# FMC.net
KiCad netlist of a schematic drawn in Altium Designer
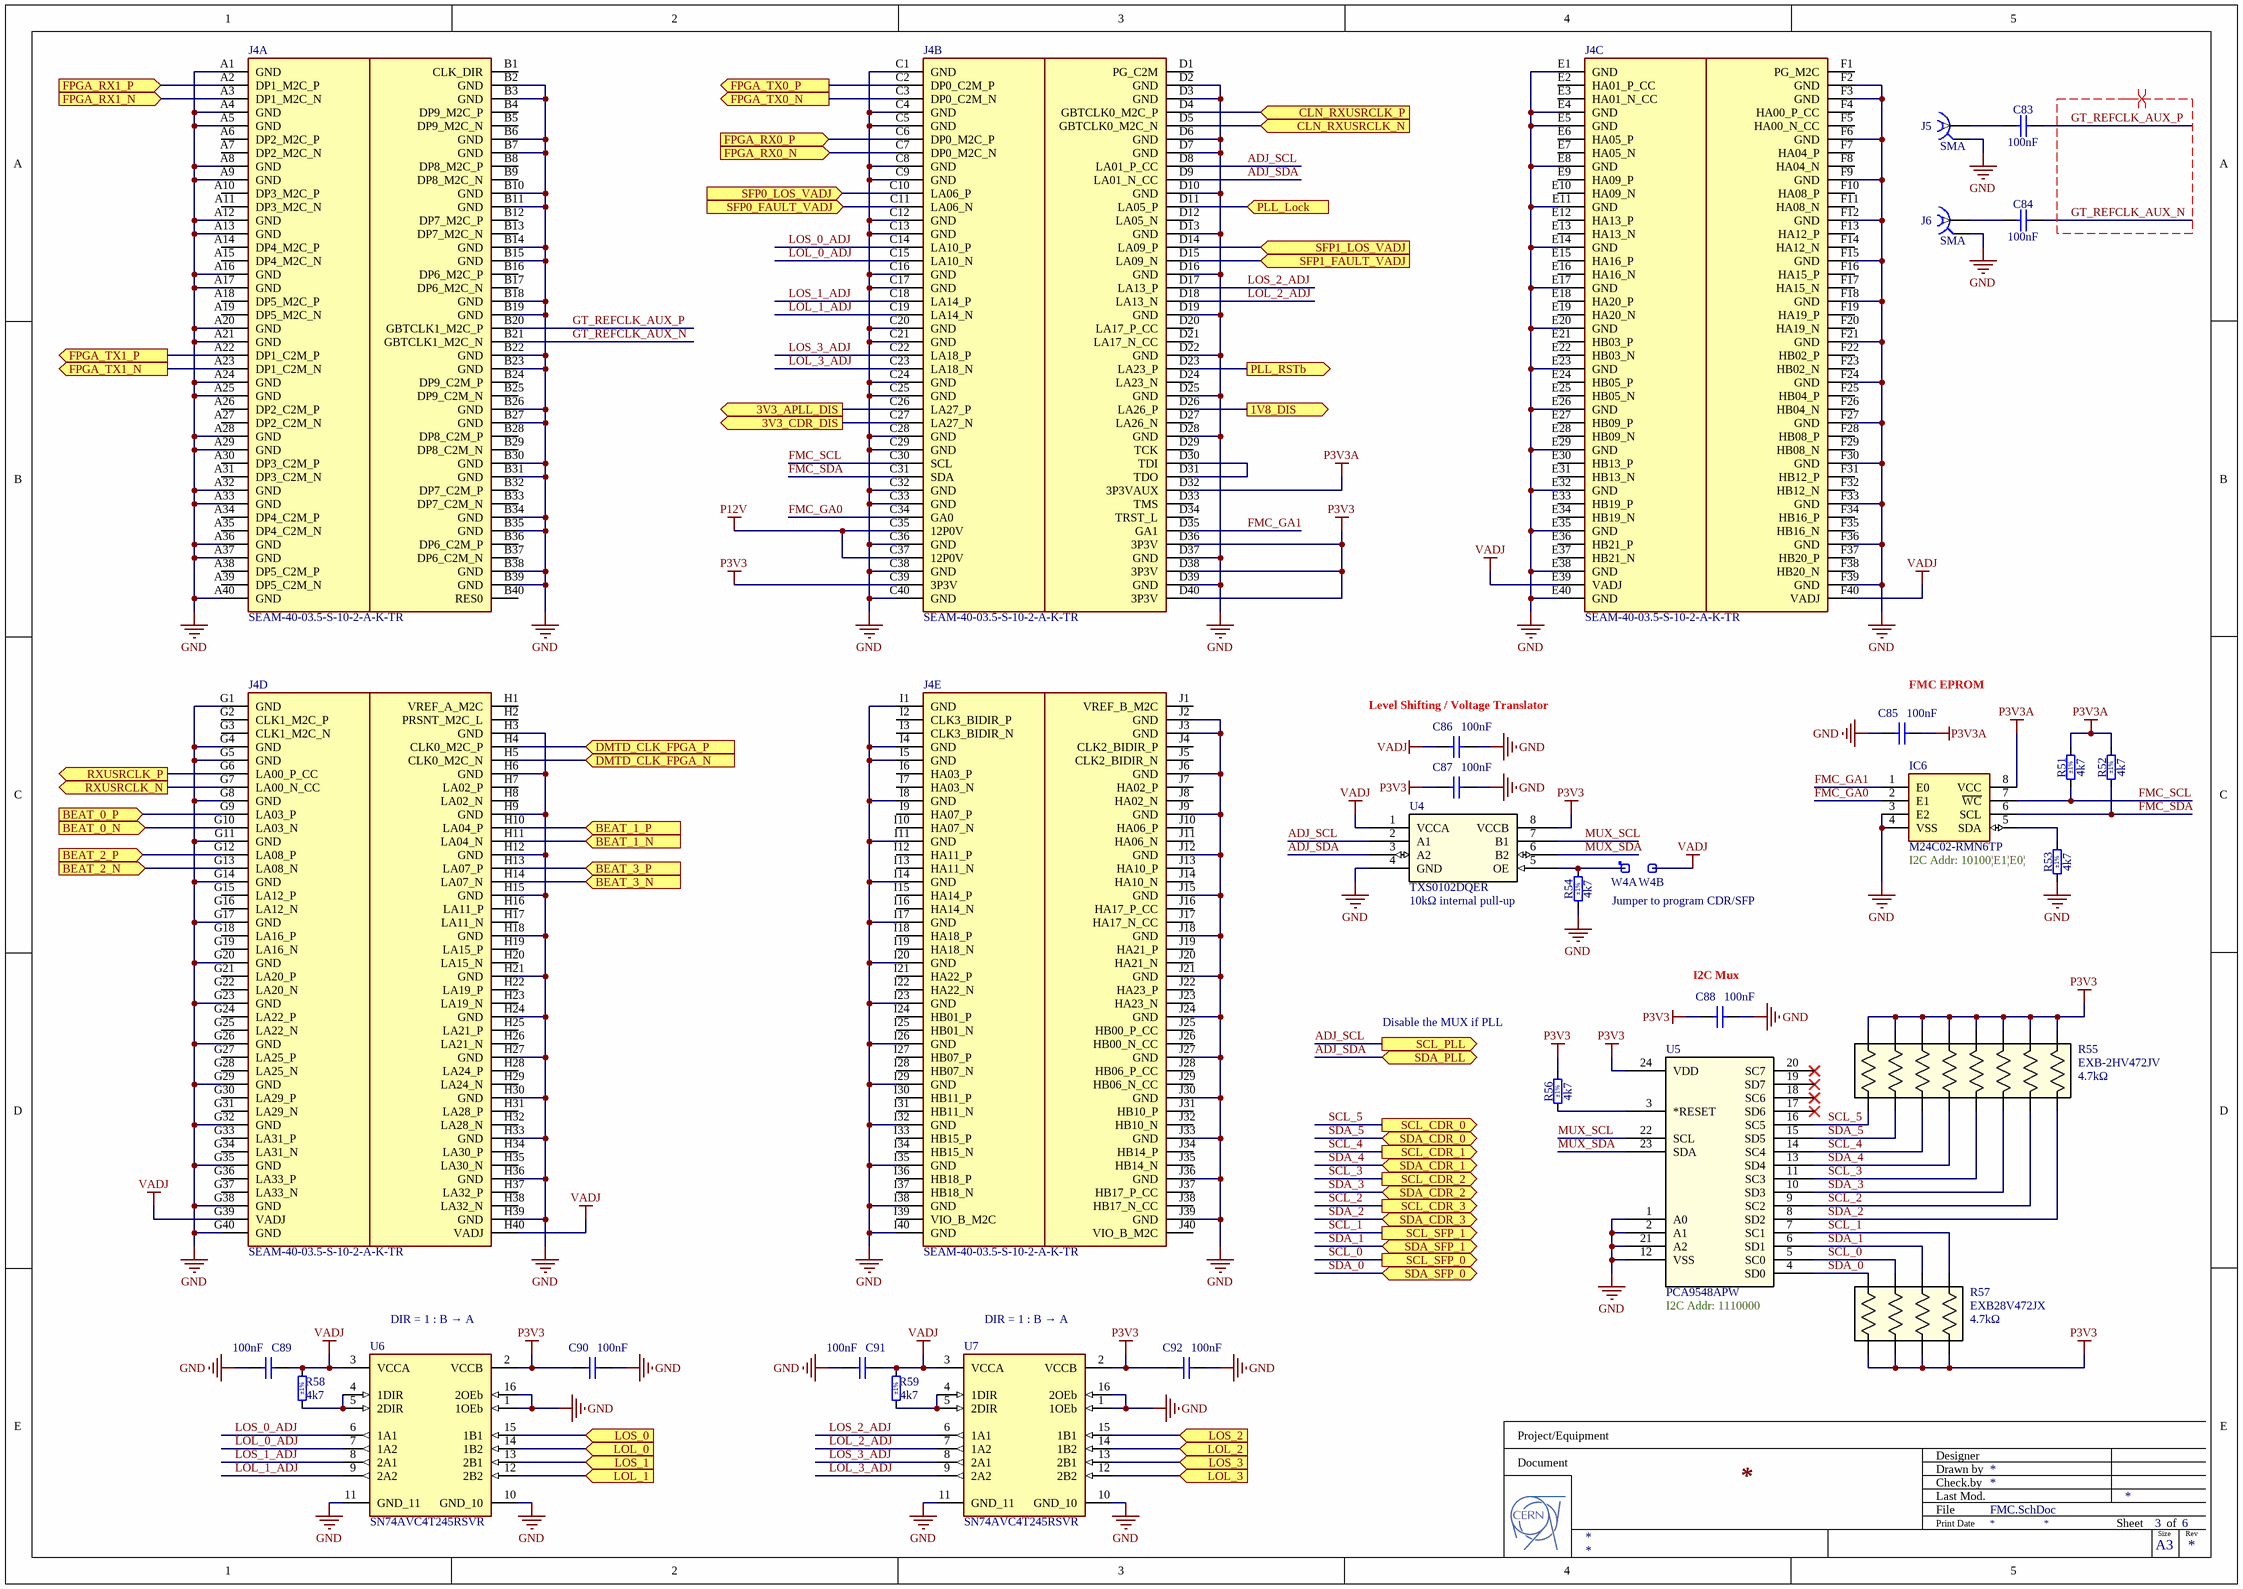
[diagram p0: FMC.SchDoc]

(export (version "E")
  (design (tool "Eeschema 10.0.6"))
  (components
    (comp (ref "C83")
      (value "100nF")
      (footprint "CAPC0603X33N")
      (description "Non-polarised capacitor")
      (fields
        (field (name "PART NUMBER") "CC0201_100NF_6.3V_10%_X7R")
        (field (name "VOLTAGE") "6.3V")
        (field (name "AUTHOR") "CERN DEM BC")
      )
      (libsource (lib "Capacitors") (part "Capacitor - non polarized"))
    )
    (comp (ref "C84")
      (value "100nF")
      (footprint "CAPC0603X33N")
      (description "Non-polarised capacitor")
      (fields
        (field (name "PART NUMBER") "CC0201_100NF_6.3V_10%_X7R")
        (field (name "VOLTAGE") "6.3V")
        (field (name "AUTHOR") "CERN DEM BC")
      )
      (libsource (lib "Capacitors") (part "Capacitor - non polarized"))
    )
    (comp (ref "C85")
      (value "100nF")
      (footprint "CAPC0603X33N")
      (description "GRM033R61C104KE14")
      (fields
        (field (name "PART NUMBER") "CC0201_100NF_6.3V_10%_X5R")
        (field (name "VOLTAGE") "6.3V")
        (field (name "AUTHOR") "CERN DEM JLC")
      )
      (libsource (lib "Capacitors") (part "Capacitor - non polarized"))
    )
    (comp (ref "C86")
      (value "100nF")
      (footprint "CAPC0603X33N")
      (description "GRM033R61C104KE14")
      (fields
        (field (name "PART NUMBER") "CC0201_100NF_6.3V_10%_X5R")
        (field (name "VOLTAGE") "6.3V")
        (field (name "AUTHOR") "CERN DEM JLC")
      )
      (libsource (lib "Capacitors") (part "Capacitor - non polarized"))
    )
    (comp (ref "C87")
      (value "100nF")
      (footprint "CAPC0603X33N")
      (description "GRM033R61C104KE14")
      (fields
        (field (name "PART NUMBER") "CC0201_100NF_6.3V_10%_X5R")
        (field (name "VOLTAGE") "6.3V")
        (field (name "AUTHOR") "CERN DEM JLC")
      )
      (libsource (lib "Capacitors") (part "Capacitor - non polarized"))
    )
    (comp (ref "C88")
      (value "100nF")
      (footprint "CAPC0603X33N")
      (description "GRM033R61C104KE14")
      (fields
        (field (name "PART NUMBER") "CC0201_100NF_6.3V_10%_X5R")
        (field (name "VOLTAGE") "6.3V")
        (field (name "AUTHOR") "CERN DEM JLC")
      )
      (libsource (lib "Capacitors") (part "Capacitor - non polarized"))
    )
    (comp (ref "C89")
      (value "100nF")
      (footprint "CAPC0603X33N")
      (description "GRM033R61C104KE14")
      (fields
        (field (name "PART NUMBER") "CC0201_100NF_6.3V_10%_X5R")
        (field (name "VOLTAGE") "6.3V")
        (field (name "AUTHOR") "CERN DEM JLC")
      )
      (libsource (lib "Capacitors") (part "Capacitor - non polarized"))
    )
    (comp (ref "C90")
      (value "100nF")
      (footprint "CAPC0603X33N")
      (description "GRM033R61C104KE14")
      (fields
        (field (name "PART NUMBER") "CC0201_100NF_6.3V_10%_X5R")
        (field (name "VOLTAGE") "6.3V")
        (field (name "AUTHOR") "CERN DEM JLC")
      )
      (libsource (lib "Capacitors") (part "Capacitor - non polarized"))
    )
    (comp (ref "C91")
      (value "100nF")
      (footprint "CAPC0603X33N")
      (description "GRM033R61C104KE14")
      (fields
        (field (name "PART NUMBER") "CC0201_100NF_6.3V_10%_X5R")
        (field (name "VOLTAGE") "6.3V")
        (field (name "AUTHOR") "CERN DEM JLC")
      )
      (libsource (lib "Capacitors") (part "Capacitor - non polarized"))
    )
    (comp (ref "C92")
      (value "100nF")
      (footprint "CAPC0603X33N")
      (description "GRM033R61C104KE14")
      (fields
        (field (name "PART NUMBER") "CC0201_100NF_6.3V_10%_X5R")
        (field (name "VOLTAGE") "6.3V")
        (field (name "AUTHOR") "CERN DEM JLC")
      )
      (libsource (lib "Capacitors") (part "Capacitor - non polarized"))
    )
    (comp (ref "IC6")
      (value "M24C02-RMN6TP")
      (footprint "SamacSys:SOIC127P600X175-8N")
      (description "Integrated Circuit")
      (fields (field (name "MOUSER PART NUMBER") "511-M24C02-RMN6TP"))
      (libsource (lib "SamacSys") (part "M24C02-RMN6TP"))
    )
    (comp (ref "J4")
      (value "SEAM-40-03.5-S-10-2-A-K-TR")
      (footprint "SAMTEC_SEAM-40-03.5-S-10-2-A-K-TR")
      (fields (field (name "MF") "Samtec"))
      (libsource (lib "SEAM-40-03.5-S-10-2-A-K-TR") (part "SEAM-40-03.5-S-10-2-A-K-TR"))
    )
    (comp (ref "J5")
      (value "SMA")
      (footprint "SAMTEC_SMA-J-P-H-ST-MT1")
      (fields
        (field (name "PART NUMBER") "SAMTEC_SMA-J-P-H-ST-MT1")
        (field (name "MANUFACTURER") "SAMTEC")
        (field (name "MANUFACTURER PART NUMBER") "SMA-J-P-H-ST-MT1")
        (field (name "AUTHOR") "CERN DEM HF")
      )
      (libsource (lib "Connectors") (part "Coax_1Female_1Shield"))
    )
    (comp (ref "J6")
      (value "SMA")
      (footprint "SAMTEC_SMA-J-P-H-ST-MT1")
      (fields
        (field (name "PART NUMBER") "SAMTEC_SMA-J-P-H-ST-MT1")
        (field (name "MANUFACTURER") "SAMTEC")
        (field (name "MANUFACTURER PART NUMBER") "SMA-J-P-H-ST-MT1")
        (field (name "AUTHOR") "CERN DEM HF")
      )
      (libsource (lib "Connectors") (part "Coax_1Female_1Shield"))
    )
    (comp (ref "R51")
      (value "4k7")
      (footprint "RESC1005X40N")
      (description "Resistor - 1%")
      (fields
        (field (name "TOLERANCE") "±1%")
        (field (name "PART NUMBER") "R0402_4K7_1%_0.0625W_100PPM")
        (field (name "POWER") "0.0625W")
        (field (name "AUTHOR") "CERN DEM JLC")
      )
      (libsource (lib "Resistors") (part "Resistor - 1%"))
    )
    (comp (ref "R52")
      (value "4k7")
      (footprint "RESC1005X40N")
      (description "Resistor - 1%")
      (fields
        (field (name "TOLERANCE") "±1%")
        (field (name "PART NUMBER") "R0402_4K7_1%_0.0625W_100PPM")
        (field (name "POWER") "0.0625W")
        (field (name "AUTHOR") "CERN DEM JLC")
      )
      (libsource (lib "Resistors") (part "Resistor - 1%"))
    )
    (comp (ref "R53")
      (value "4k7")
      (footprint "RESC1005X40N")
      (description "Resistor - 1%")
      (fields
        (field (name "TOLERANCE") "±1%")
        (field (name "PART NUMBER") "R0402_4K7_1%_0.0625W_100PPM")
        (field (name "POWER") "0.0625W")
        (field (name "AUTHOR") "CERN DEM JLC")
      )
      (libsource (lib "Resistors") (part "Resistor - 1%"))
    )
    (comp (ref "R54")
      (value "4k7")
      (footprint "RESC1005X40N")
      (description "Resistor - 1%")
      (fields
        (field (name "TOLERANCE") "±1%")
        (field (name "PART NUMBER") "R0402_4K7_1%_0.0625W_100PPM")
        (field (name "POWER") "0.0625W")
        (field (name "AUTHOR") "CERN DEM JLC")
      )
      (libsource (lib "Resistors") (part "Resistor - 1%"))
    )
    (comp (ref "R55")
      (value "EXB-2HV472JV")
      (footprint "RES_EXB2HV")
      (description "No Description Available")
      (libsource (lib "EXB-2HV472JV") (part "EXB-2HV472JV"))
    )
    (comp (ref "R56")
      (value "4k7")
      (footprint "RESC1005X40N")
      (description "Resistor - 1%")
      (fields
        (field (name "TOLERANCE") "±1%")
        (field (name "PART NUMBER") "R0402_4K7_1%_0.0625W_100PPM")
        (field (name "POWER") "0.0625W")
        (field (name "AUTHOR") "CERN DEM JLC")
      )
      (libsource (lib "Resistors") (part "Resistor - 1%"))
    )
    (comp (ref "R57")
      (value "EXB28V472JX")
      (footprint "C_ARRAY_EXB28V_PAN")
      (description "No Description Available")
      (libsource (lib "EXB28V472JX") (part "EXB28V472JX"))
    )
    (comp (ref "R58")
      (value "4k7")
      (footprint "RESC1005X40N")
      (description "Resistor - 1%")
      (fields
        (field (name "TOLERANCE") "±1%")
        (field (name "PART NUMBER") "R0402_4K7_1%_0.0625W_100PPM")
        (field (name "POWER") "0.0625W")
        (field (name "AUTHOR") "CERN DEM JLC")
      )
      (libsource (lib "Resistors") (part "Resistor - 1%"))
    )
    (comp (ref "R59")
      (value "4k7")
      (footprint "RESC1005X40N")
      (description "Resistor - 1%")
      (fields
        (field (name "TOLERANCE") "±1%")
        (field (name "PART NUMBER") "R0402_4K7_1%_0.0625W_100PPM")
        (field (name "POWER") "0.0625W")
        (field (name "AUTHOR") "CERN DEM JLC")
      )
      (libsource (lib "Resistors") (part "Resistor - 1%"))
    )
    (comp (ref "U4")
      (value "TXS0102DQER")
      (footprint "TXS0102DQER:DQE8_TEX")
      (description "No Description Available")
      (libsource (lib "TXS0102DQER") (part "TXS0102DQER"))
    )
    (comp (ref "U5")
      (value "PCA9548APW")
      (footprint "PCA9548APW:SOT355-1_NXP")
      (description "No Description Available")
      (libsource (lib "PCA9548APW") (part "PCA9548APW"))
    )
    (comp (ref "U6")
      (value "SN74AVC4T245RSVR")
      (footprint "QFN40P260X180X55-16N:QFN40P260X180X55-16N")
      (fields (field (name "MF") "Texas Instruments"))
      (libsource (lib "SN74AVC4T245RSVR") (part "SN74AVC4T245RSVR"))
    )
    (comp (ref "U7")
      (value "SN74AVC4T245RSVR")
      (footprint "QFN40P260X180X55-16N:QFN40P260X180X55-16N")
      (fields (field (name "MF") "Texas Instruments"))
      (libsource (lib "SN74AVC4T245RSVR") (part "SN74AVC4T245RSVR"))
    )
    (comp (ref "W4")
      (value "Header 2")
      (footprint "SAMTEC_HTSW-102-23-L-S")
      (description "2 Mini Wire-Wrap Contact Strip Header")
      (fields
        (field (name "PART NUMBER") "SAMTEC_HTSW-102-23-L-S")
        (field (name "MANUFACTURER") "SAMTEC")
        (field (name "AUTHOR") "CERN DEM JLC")
      )
      (libsource (lib "Connectors") (part "Wire-Wrap Contact x2"))
    )
  )
  (nets
    (net (code "1") (name "/1V8_DIS") (class "Default")
      (node (ref "J4") (pin "D26") (pinfunction "LA26_P_D26") (pintype "passive"))
    )
    (net (code "2") (name "/3V3_APLL_DIS") (class "Default")
      (node (ref "J4") (pin "C26") (pinfunction "LA27_P_C26") (pintype "passive"))
    )
    (net (code "3") (name "/3V3_CDR_DIS") (class "Default")
      (node (ref "J4") (pin "C27") (pinfunction "LA27_N_C27") (pintype "passive"))
    )
    (net (code "4") (name "/ADJ_SCL") (class "Default")
      (node (ref "J4") (pin "D8") (pinfunction "LA01_P_CC_D8") (pintype "passive"))
      (node (ref "U4") (pin "2") (pinfunction "A1_2") (pintype "passive"))
    )
    (net (code "5") (name "/ADJ_SDA") (class "Default")
      (node (ref "J4") (pin "D9") (pinfunction "LA01_N_CC_D9") (pintype "passive"))
      (node (ref "U4") (pin "3") (pinfunction "A2_3") (pintype "bidirectional"))
    )
    (net (code "6") (name "/BEAT_0_N") (class "Default")
      (node (ref "J4") (pin "G10") (pinfunction "LA03_N_G10") (pintype "passive"))
    )
    (net (code "7") (name "/BEAT_0_P") (class "Default")
      (node (ref "J4") (pin "G9") (pinfunction "LA03_P_G9") (pintype "passive"))
    )
    (net (code "8") (name "/BEAT_1_N") (class "Default")
      (node (ref "J4") (pin "H11") (pinfunction "LA04_N_H11") (pintype "passive"))
    )
    (net (code "9") (name "/BEAT_1_P") (class "Default")
      (node (ref "J4") (pin "H10") (pinfunction "LA04_P_H10") (pintype "passive"))
    )
    (net (code "10") (name "/BEAT_2_N") (class "Default")
      (node (ref "J4") (pin "G13") (pinfunction "LA08_N_G13") (pintype "passive"))
    )
    (net (code "11") (name "/BEAT_2_P") (class "Default")
      (node (ref "J4") (pin "G12") (pinfunction "LA08_P_G12") (pintype "passive"))
    )
    (net (code "12") (name "/BEAT_3_N") (class "Default")
      (node (ref "J4") (pin "H14") (pinfunction "LA07_N_H14") (pintype "passive"))
    )
    (net (code "13") (name "/BEAT_3_P") (class "Default")
      (node (ref "J4") (pin "H13") (pinfunction "LA07_P_H13") (pintype "passive"))
    )
    (net (code "14") (name "/CLN_RXUSRCLK_N") (class "Default")
      (node (ref "J4") (pin "D5") (pinfunction "GBTCLK0_M2C_N_D5") (pintype "passive"))
    )
    (net (code "15") (name "/CLN_RXUSRCLK_P") (class "Default")
      (node (ref "J4") (pin "D4") (pinfunction "GBTCLK0_M2C_P_D4") (pintype "passive"))
    )
    (net (code "16") (name "/DMTD_CLK_FPGA_N") (class "Default")
      (node (ref "J4") (pin "H5") (pinfunction "CLK0_M2C_N_H5") (pintype "passive"))
    )
    (net (code "17") (name "/DMTD_CLK_FPGA_P") (class "Default")
      (node (ref "J4") (pin "H4") (pinfunction "CLK0_M2C_P_H4") (pintype "passive"))
    )
    (net (code "18") (name "/FMC_GA0") (class "Default")
      (node (ref "IC6") (pin "2") (pinfunction "E1_2") (pintype "passive"))
      (node (ref "J4") (pin "C34") (pinfunction "GA0_C34") (pintype "passive"))
    )
    (net (code "19") (name "/FMC_GA1") (class "Default")
      (node (ref "IC6") (pin "1") (pinfunction "E0_1") (pintype "passive"))
      (node (ref "J4") (pin "D35") (pinfunction "GA1_D35") (pintype "passive"))
    )
    (net (code "20") (name "/FMC_SCL") (class "Default")
      (node (ref "IC6") (pin "7") (pinfunction "~{WC}_7") (pintype "passive"))
      (node (ref "J4") (pin "C30") (pinfunction "SCL_C30") (pintype "passive"))
      (node (ref "R51") (pin "1") (pinfunction "1_1") (pintype "passive"))
    )
    (net (code "21") (name "/FMC_SDA") (class "Default")
      (node (ref "IC6") (pin "6") (pinfunction "SCL_6") (pintype "passive"))
      (node (ref "J4") (pin "C31") (pinfunction "SDA_C31") (pintype "passive"))
      (node (ref "R52") (pin "1") (pinfunction "1_1") (pintype "passive"))
    )
    (net (code "22") (name "/FPGA_RX0_N") (class "Default")
      (node (ref "J4") (pin "C7") (pinfunction "DP0_M2C_N_C7") (pintype "passive"))
    )
    (net (code "23") (name "/FPGA_RX0_P") (class "Default")
      (node (ref "J4") (pin "C6") (pinfunction "DP0_M2C_P_C6") (pintype "passive"))
    )
    (net (code "24") (name "/FPGA_RX1_N") (class "Default")
      (node (ref "J4") (pin "A3") (pinfunction "DP1_M2C_N_A3") (pintype "passive"))
    )
    (net (code "25") (name "/FPGA_RX1_P") (class "Default")
      (node (ref "J4") (pin "A2") (pinfunction "DP1_M2C_P_A2") (pintype "passive"))
    )
    (net (code "26") (name "/FPGA_TX0_N") (class "Default")
      (node (ref "J4") (pin "C3") (pinfunction "DP0_C2M_N_C3") (pintype "passive"))
    )
    (net (code "27") (name "/FPGA_TX0_P") (class "Default")
      (node (ref "J4") (pin "C2") (pinfunction "DP0_C2M_P_C2") (pintype "passive"))
    )
    (net (code "28") (name "/FPGA_TX1_N") (class "Default")
      (node (ref "J4") (pin "A23") (pinfunction "DP1_C2M_N_A23") (pintype "passive"))
    )
    (net (code "29") (name "/FPGA_TX1_P") (class "Default")
      (node (ref "J4") (pin "A22") (pinfunction "DP1_C2M_P_A22") (pintype "passive"))
    )
    (net (code "30") (name "/GT_REFCLK_AUX_N") (class "Default")
      (node (ref "C84") (pin "1") (pinfunction "1_1") (pintype "passive"))
      (node (ref "J4") (pin "B21") (pinfunction "GBTCLK1_M2C_N_B21") (pintype "passive"))
    )
    (net (code "31") (name "/GT_REFCLK_AUX_P") (class "Default")
      (node (ref "C83") (pin "1") (pinfunction "1_1") (pintype "passive"))
      (node (ref "J4") (pin "B20") (pinfunction "GBTCLK1_M2C_P_B20") (pintype "passive"))
    )
    (net (code "32") (name "/LOL_0") (class "Default")
      (node (ref "U6") (pin "14") (pinfunction "1B2_14") (pintype "input"))
    )
    (net (code "33") (name "/LOL_0_ADJ") (class "Default")
      (node (ref "J4") (pin "C15") (pinfunction "LA10_N_C15") (pintype "passive"))
      (node (ref "U6") (pin "7") (pinfunction "1A2_7") (pintype "output"))
    )
    (net (code "34") (name "/LOL_1") (class "Default")
      (node (ref "U6") (pin "12") (pinfunction "2B2_12") (pintype "input"))
    )
    (net (code "35") (name "/LOL_1_ADJ") (class "Default")
      (node (ref "J4") (pin "C19") (pinfunction "LA14_N_C19") (pintype "passive"))
      (node (ref "U6") (pin "9") (pinfunction "2A2_9") (pintype "output"))
    )
    (net (code "36") (name "/LOL_2") (class "Default")
      (node (ref "U7") (pin "14") (pinfunction "1B2_14") (pintype "input"))
    )
    (net (code "37") (name "/LOL_2_ADJ") (class "Default")
      (node (ref "J4") (pin "D18") (pinfunction "LA13_N_D18") (pintype "passive"))
      (node (ref "U7") (pin "7") (pinfunction "1A2_7") (pintype "output"))
    )
    (net (code "38") (name "/LOL_3") (class "Default")
      (node (ref "U7") (pin "12") (pinfunction "2B2_12") (pintype "input"))
    )
    (net (code "39") (name "/LOL_3_ADJ") (class "Default")
      (node (ref "J4") (pin "C23") (pinfunction "LA18_N_C23") (pintype "passive"))
      (node (ref "U7") (pin "9") (pinfunction "2A2_9") (pintype "output"))
    )
    (net (code "40") (name "/LOS_0") (class "Default")
      (node (ref "U6") (pin "15") (pinfunction "1B1_15") (pintype "input"))
    )
    (net (code "41") (name "/LOS_0_ADJ") (class "Default")
      (node (ref "J4") (pin "C14") (pinfunction "LA10_P_C14") (pintype "passive"))
      (node (ref "U6") (pin "6") (pinfunction "1A1_6") (pintype "output"))
    )
    (net (code "42") (name "/LOS_1") (class "Default")
      (node (ref "U6") (pin "13") (pinfunction "2B1_13") (pintype "input"))
    )
    (net (code "43") (name "/LOS_1_ADJ") (class "Default")
      (node (ref "J4") (pin "C18") (pinfunction "LA14_P_C18") (pintype "passive"))
      (node (ref "U6") (pin "8") (pinfunction "2A1_8") (pintype "output"))
    )
    (net (code "44") (name "/LOS_2") (class "Default")
      (node (ref "U7") (pin "15") (pinfunction "1B1_15") (pintype "input"))
    )
    (net (code "45") (name "/LOS_2_ADJ") (class "Default")
      (node (ref "J4") (pin "D17") (pinfunction "LA13_P_D17") (pintype "passive"))
      (node (ref "U7") (pin "6") (pinfunction "1A1_6") (pintype "output"))
    )
    (net (code "46") (name "/LOS_3") (class "Default")
      (node (ref "U7") (pin "13") (pinfunction "2B1_13") (pintype "input"))
    )
    (net (code "47") (name "/LOS_3_ADJ") (class "Default")
      (node (ref "J4") (pin "C22") (pinfunction "LA18_P_C22") (pintype "passive"))
      (node (ref "U7") (pin "8") (pinfunction "2A1_8") (pintype "output"))
    )
    (net (code "48") (name "/MUX_SCL") (class "Default")
      (node (ref "U4") (pin "7") (pinfunction "B1_7") (pintype "passive"))
      (node (ref "U5") (pin "22") (pinfunction "SCL_22") (pintype "passive"))
    )
    (net (code "49") (name "/MUX_SDA") (class "Default")
      (node (ref "U4") (pin "6") (pinfunction "B2_6") (pintype "bidirectional"))
      (node (ref "U5") (pin "23") (pinfunction "SDA_23") (pintype "passive"))
    )
    (net (code "50") (name "/PLL_Lock") (class "Default")
      (node (ref "J4") (pin "D11") (pinfunction "LA05_P_D11") (pintype "passive"))
    )
    (net (code "51") (name "/PLL_RSTb") (class "Default")
      (node (ref "J4") (pin "D23") (pinfunction "LA23_P_D23") (pintype "passive"))
    )
    (net (code "52") (name "/RXUSRCLK_N") (class "Default")
      (node (ref "J4") (pin "G7") (pinfunction "LA00_N_CC_G7") (pintype "passive"))
    )
    (net (code "53") (name "/RXUSRCLK_P") (class "Default")
      (node (ref "J4") (pin "G6") (pinfunction "LA00_P_CC_G6") (pintype "passive"))
    )
    (net (code "54") (name "/SCL_0") (class "Default")
      (node (ref "R57") (pin "7") (pinfunction "7_7") (pintype "passive"))
      (node (ref "U5") (pin "5") (pinfunction "SC0_5") (pintype "passive"))
    )
    (net (code "55") (name "/SCL_1") (class "Default")
      (node (ref "R57") (pin "5") (pinfunction "5_5") (pintype "passive"))
      (node (ref "U5") (pin "7") (pinfunction "SC1_7") (pintype "passive"))
    )
    (net (code "56") (name "/SCL_2") (class "Default")
      (node (ref "R55") (pin "7") (pinfunction "7_7") (pintype "passive"))
      (node (ref "U5") (pin "9") (pinfunction "SC2_9") (pintype "passive"))
    )
    (net (code "57") (name "/SCL_3") (class "Default")
      (node (ref "R55") (pin "5") (pinfunction "5_5") (pintype "passive"))
      (node (ref "U5") (pin "11") (pinfunction "SC3_11") (pintype "passive"))
    )
    (net (code "58") (name "/SCL_4") (class "Default")
      (node (ref "R55") (pin "3") (pinfunction "3_3") (pintype "passive"))
      (node (ref "U5") (pin "14") (pinfunction "SC4_14") (pintype "passive"))
    )
    (net (code "59") (name "/SCL_5") (class "Default")
      (node (ref "R55") (pin "1") (pinfunction "1_1") (pintype "passive"))
      (node (ref "U5") (pin "16") (pinfunction "SC5_16") (pintype "passive"))
    )
    (net (code "60") (name "/SDA_0") (class "Default")
      (node (ref "R57") (pin "8") (pinfunction "8_8") (pintype "passive"))
      (node (ref "U5") (pin "4") (pinfunction "SD0_4") (pintype "passive"))
    )
    (net (code "61") (name "/SDA_1") (class "Default")
      (node (ref "R57") (pin "6") (pinfunction "6_6") (pintype "passive"))
      (node (ref "U5") (pin "6") (pinfunction "SD1_6") (pintype "passive"))
    )
    (net (code "62") (name "/SDA_2") (class "Default")
      (node (ref "R55") (pin "8") (pinfunction "8_8") (pintype "passive"))
      (node (ref "U5") (pin "8") (pinfunction "SD2_8") (pintype "passive"))
    )
    (net (code "63") (name "/SDA_3") (class "Default")
      (node (ref "R55") (pin "6") (pinfunction "6_6") (pintype "passive"))
      (node (ref "U5") (pin "10") (pinfunction "SD3_10") (pintype "passive"))
    )
    (net (code "64") (name "/SDA_4") (class "Default")
      (node (ref "R55") (pin "4") (pinfunction "4_4") (pintype "passive"))
      (node (ref "U5") (pin "13") (pinfunction "SD4_13") (pintype "passive"))
    )
    (net (code "65") (name "/SDA_5") (class "Default")
      (node (ref "R55") (pin "2") (pinfunction "2_2") (pintype "passive"))
      (node (ref "U5") (pin "15") (pinfunction "SD5_15") (pintype "passive"))
    )
    (net (code "66") (name "/SFP0_FAULT_VADJ") (class "Default")
      (node (ref "J4") (pin "C11") (pinfunction "LA06_N_C11") (pintype "passive"))
    )
    (net (code "67") (name "/SFP0_LOS_VADJ") (class "Default")
      (node (ref "J4") (pin "C10") (pinfunction "LA06_P_C10") (pintype "passive"))
    )
    (net (code "68") (name "/SFP1_FAULT_VADJ") (class "Default")
      (node (ref "J4") (pin "D15") (pinfunction "LA09_N_D15") (pintype "passive"))
    )
    (net (code "69") (name "/SFP1_LOS_VADJ") (class "Default")
      (node (ref "J4") (pin "D14") (pinfunction "LA09_P_D14") (pintype "passive"))
    )
    (net (code "70") (name "GND") (class "Default")
      (node (ref "C85") (pin "1") (pinfunction "1_1") (pintype "passive"))
      (node (ref "C86") (pin "1") (pinfunction "1_1") (pintype "passive"))
      (node (ref "C87") (pin "1") (pinfunction "1_1") (pintype "passive"))
      (node (ref "C88") (pin "1") (pinfunction "1_1") (pintype "passive"))
      (node (ref "C89") (pin "1") (pinfunction "1_1") (pintype "passive"))
      (node (ref "C90") (pin "1") (pinfunction "1_1") (pintype "passive"))
      (node (ref "C91") (pin "1") (pinfunction "1_1") (pintype "passive"))
      (node (ref "C92") (pin "1") (pinfunction "1_1") (pintype "passive"))
      (node (ref "IC6") (pin "3") (pinfunction "E2_3") (pintype "passive"))
      (node (ref "IC6") (pin "4") (pinfunction "VSS_4") (pintype "power_in"))
      (node (ref "J4") (pin "A1") (pinfunction "GND_A1") (pintype "passive"))
      (node (ref "J4") (pin "A12") (pinfunction "GND_A12") (pintype "passive"))
      (node (ref "J4") (pin "A13") (pinfunction "GND_A13") (pintype "passive"))
      (node (ref "J4") (pin "A16") (pinfunction "GND_A16") (pintype "passive"))
      (node (ref "J4") (pin "A17") (pinfunction "GND_A17") (pintype "passive"))
      (node (ref "J4") (pin "A20") (pinfunction "GND_A20") (pintype "passive"))
      (node (ref "J4") (pin "A21") (pinfunction "GND_A21") (pintype "passive"))
      (node (ref "J4") (pin "A24") (pinfunction "GND_A24") (pintype "passive"))
      (node (ref "J4") (pin "A25") (pinfunction "GND_A25") (pintype "passive"))
      (node (ref "J4") (pin "A28") (pinfunction "GND_A28") (pintype "passive"))
      (node (ref "J4") (pin "A29") (pinfunction "GND_A29") (pintype "passive"))
      (node (ref "J4") (pin "A32") (pinfunction "GND_A32") (pintype "passive"))
      (node (ref "J4") (pin "A33") (pinfunction "GND_A33") (pintype "passive"))
      (node (ref "J4") (pin "A36") (pinfunction "GND_A36") (pintype "passive"))
      (node (ref "J4") (pin "A37") (pinfunction "GND_A37") (pintype "passive"))
      (node (ref "J4") (pin "A4") (pinfunction "GND_A4") (pintype "passive"))
      (node (ref "J4") (pin "A40") (pinfunction "GND_A40") (pintype "passive"))
      (node (ref "J4") (pin "A5") (pinfunction "GND_A5") (pintype "passive"))
      (node (ref "J4") (pin "A8") (pinfunction "GND_A8") (pintype "passive"))
      (node (ref "J4") (pin "A9") (pinfunction "GND_A9") (pintype "passive"))
      (node (ref "J4") (pin "B10") (pinfunction "GND_B10") (pintype "passive"))
      (node (ref "J4") (pin "B11") (pinfunction "GND_B11") (pintype "passive"))
      (node (ref "J4") (pin "B14") (pinfunction "GND_B14") (pintype "passive"))
      (node (ref "J4") (pin "B15") (pinfunction "GND_B15") (pintype "passive"))
      (node (ref "J4") (pin "B18") (pinfunction "GND_B18") (pintype "passive"))
      (node (ref "J4") (pin "B19") (pinfunction "GND_B19") (pintype "passive"))
      (node (ref "J4") (pin "B2") (pinfunction "GND_B2") (pintype "passive"))
      (node (ref "J4") (pin "B22") (pinfunction "GND_B22") (pintype "passive"))
      (node (ref "J4") (pin "B23") (pinfunction "GND_B23") (pintype "passive"))
      (node (ref "J4") (pin "B26") (pinfunction "GND_B26") (pintype "passive"))
      (node (ref "J4") (pin "B27") (pinfunction "GND_B27") (pintype "passive"))
      (node (ref "J4") (pin "B3") (pinfunction "GND_B3") (pintype "passive"))
      (node (ref "J4") (pin "B30") (pinfunction "GND_B30") (pintype "passive"))
      (node (ref "J4") (pin "B31") (pinfunction "GND_B31") (pintype "passive"))
      (node (ref "J4") (pin "B34") (pinfunction "GND_B34") (pintype "passive"))
      (node (ref "J4") (pin "B35") (pinfunction "GND_B35") (pintype "passive"))
      (node (ref "J4") (pin "B38") (pinfunction "GND_B38") (pintype "passive"))
      (node (ref "J4") (pin "B39") (pinfunction "GND_B39") (pintype "passive"))
      (node (ref "J4") (pin "B6") (pinfunction "GND_B6") (pintype "passive"))
      (node (ref "J4") (pin "B7") (pinfunction "GND_B7") (pintype "passive"))
      (node (ref "J4") (pin "C1") (pinfunction "GND_C1") (pintype "passive"))
      (node (ref "J4") (pin "C12") (pinfunction "GND_C12") (pintype "passive"))
      (node (ref "J4") (pin "C13") (pinfunction "GND_C13") (pintype "passive"))
      (node (ref "J4") (pin "C16") (pinfunction "GND_C16") (pintype "passive"))
      (node (ref "J4") (pin "C17") (pinfunction "GND_C17") (pintype "passive"))
      (node (ref "J4") (pin "C20") (pinfunction "GND_C20") (pintype "passive"))
      (node (ref "J4") (pin "C21") (pinfunction "GND_C21") (pintype "passive"))
      (node (ref "J4") (pin "C24") (pinfunction "GND_C24") (pintype "passive"))
      (node (ref "J4") (pin "C25") (pinfunction "GND_C25") (pintype "passive"))
      (node (ref "J4") (pin "C28") (pinfunction "GND_C28") (pintype "passive"))
      (node (ref "J4") (pin "C29") (pinfunction "GND_C29") (pintype "passive"))
      (node (ref "J4") (pin "C32") (pinfunction "GND_C32") (pintype "passive"))
      (node (ref "J4") (pin "C33") (pinfunction "GND_C33") (pintype "passive"))
      (node (ref "J4") (pin "C36") (pinfunction "GND_C36") (pintype "passive"))
      (node (ref "J4") (pin "C38") (pinfunction "GND_C38") (pintype "passive"))
      (node (ref "J4") (pin "C4") (pinfunction "GND_C4") (pintype "passive"))
      (node (ref "J4") (pin "C40") (pinfunction "GND_C40") (pintype "passive"))
      (node (ref "J4") (pin "C5") (pinfunction "GND_C5") (pintype "passive"))
      (node (ref "J4") (pin "C8") (pinfunction "GND_C8") (pintype "passive"))
      (node (ref "J4") (pin "C9") (pinfunction "GND_C9") (pintype "passive"))
      (node (ref "J4") (pin "D10") (pinfunction "GND_D10") (pintype "passive"))
      (node (ref "J4") (pin "D13") (pinfunction "GND_D13") (pintype "passive"))
      (node (ref "J4") (pin "D16") (pinfunction "GND_D16") (pintype "passive"))
      (node (ref "J4") (pin "D19") (pinfunction "GND_D19") (pintype "passive"))
      (node (ref "J4") (pin "D2") (pinfunction "GND_D2") (pintype "passive"))
      (node (ref "J4") (pin "D22") (pinfunction "GND_D22") (pintype "passive"))
      (node (ref "J4") (pin "D25") (pinfunction "GND_D25") (pintype "passive"))
      (node (ref "J4") (pin "D28") (pinfunction "GND_D28") (pintype "passive"))
      (node (ref "J4") (pin "D3") (pinfunction "GND_D3") (pintype "passive"))
      (node (ref "J4") (pin "D37") (pinfunction "GND_D37") (pintype "passive"))
      (node (ref "J4") (pin "D39") (pinfunction "GND_D39") (pintype "passive"))
      (node (ref "J4") (pin "D6") (pinfunction "GND_D6") (pintype "passive"))
      (node (ref "J4") (pin "D7") (pinfunction "GND_D7") (pintype "passive"))
      (node (ref "J4") (pin "E1") (pinfunction "GND_E1") (pintype "passive"))
      (node (ref "J4") (pin "E11") (pinfunction "GND_E11") (pintype "passive"))
      (node (ref "J4") (pin "E14") (pinfunction "GND_E14") (pintype "passive"))
      (node (ref "J4") (pin "E17") (pinfunction "GND_E17") (pintype "passive"))
      (node (ref "J4") (pin "E20") (pinfunction "GND_E20") (pintype "passive"))
      (node (ref "J4") (pin "E23") (pinfunction "GND_E23") (pintype "passive"))
      (node (ref "J4") (pin "E26") (pinfunction "GND_E26") (pintype "passive"))
      (node (ref "J4") (pin "E29") (pinfunction "GND_E29") (pintype "passive"))
      (node (ref "J4") (pin "E32") (pinfunction "GND_E32") (pintype "passive"))
      (node (ref "J4") (pin "E35") (pinfunction "GND_E35") (pintype "passive"))
      (node (ref "J4") (pin "E38") (pinfunction "GND_E38") (pintype "passive"))
      (node (ref "J4") (pin "E4") (pinfunction "GND_E4") (pintype "passive"))
      (node (ref "J4") (pin "E40") (pinfunction "GND_E40") (pintype "passive"))
      (node (ref "J4") (pin "E5") (pinfunction "GND_E5") (pintype "passive"))
      (node (ref "J4") (pin "E8") (pinfunction "GND_E8") (pintype "passive"))
      (node (ref "J4") (pin "F12") (pinfunction "GND_F12") (pintype "passive"))
      (node (ref "J4") (pin "F15") (pinfunction "GND_F15") (pintype "passive"))
      (node (ref "J4") (pin "F18") (pinfunction "GND_F18") (pintype "passive"))
      (node (ref "J4") (pin "F2") (pinfunction "GND_F2") (pintype "passive"))
      (node (ref "J4") (pin "F21") (pinfunction "GND_F21") (pintype "passive"))
      (node (ref "J4") (pin "F24") (pinfunction "GND_F24") (pintype "passive"))
      (node (ref "J4") (pin "F27") (pinfunction "GND_F27") (pintype "passive"))
      (node (ref "J4") (pin "F3") (pinfunction "GND_F3") (pintype "passive"))
      (node (ref "J4") (pin "F30") (pinfunction "GND_F30") (pintype "passive"))
      (node (ref "J4") (pin "F33") (pinfunction "GND_F33") (pintype "passive"))
      (node (ref "J4") (pin "F36") (pinfunction "GND_F36") (pintype "passive"))
      (node (ref "J4") (pin "F39") (pinfunction "GND_F39") (pintype "passive"))
      (node (ref "J4") (pin "F6") (pinfunction "GND_F6") (pintype "passive"))
      (node (ref "J4") (pin "F9") (pinfunction "GND_F9") (pintype "passive"))
      (node (ref "J4") (pin "G1") (pinfunction "GND_G1") (pintype "passive"))
      (node (ref "J4") (pin "G11") (pinfunction "GND_G11") (pintype "passive"))
      (node (ref "J4") (pin "G14") (pinfunction "GND_G14") (pintype "passive"))
      (node (ref "J4") (pin "G17") (pinfunction "GND_G17") (pintype "passive"))
      (node (ref "J4") (pin "G20") (pinfunction "GND_G20") (pintype "passive"))
      (node (ref "J4") (pin "G23") (pinfunction "GND_G23") (pintype "passive"))
      (node (ref "J4") (pin "G26") (pinfunction "GND_G26") (pintype "passive"))
      (node (ref "J4") (pin "G29") (pinfunction "GND_G29") (pintype "passive"))
      (node (ref "J4") (pin "G32") (pinfunction "GND_G32") (pintype "passive"))
      (node (ref "J4") (pin "G35") (pinfunction "GND_G35") (pintype "passive"))
      (node (ref "J4") (pin "G38") (pinfunction "GND_G38") (pintype "passive"))
      (node (ref "J4") (pin "G4") (pinfunction "GND_G4") (pintype "passive"))
      (node (ref "J4") (pin "G40") (pinfunction "GND_G40") (pintype "passive"))
      (node (ref "J4") (pin "G5") (pinfunction "GND_G5") (pintype "passive"))
      (node (ref "J4") (pin "G8") (pinfunction "GND_G8") (pintype "passive"))
      (node (ref "J4") (pin "H12") (pinfunction "GND_H12") (pintype "passive"))
      (node (ref "J4") (pin "H15") (pinfunction "GND_H15") (pintype "passive"))
      (node (ref "J4") (pin "H18") (pinfunction "GND_H18") (pintype "passive"))
      (node (ref "J4") (pin "H21") (pinfunction "GND_H21") (pintype "passive"))
      (node (ref "J4") (pin "H24") (pinfunction "GND_H24") (pintype "passive"))
      (node (ref "J4") (pin "H27") (pinfunction "GND_H27") (pintype "passive"))
      (node (ref "J4") (pin "H3") (pinfunction "GND_H3") (pintype "passive"))
      (node (ref "J4") (pin "H30") (pinfunction "GND_H30") (pintype "passive"))
      (node (ref "J4") (pin "H33") (pinfunction "GND_H33") (pintype "passive"))
      (node (ref "J4") (pin "H36") (pinfunction "GND_H36") (pintype "passive"))
      (node (ref "J4") (pin "H39") (pinfunction "GND_H39") (pintype "passive"))
      (node (ref "J4") (pin "H6") (pinfunction "GND_H6") (pintype "passive"))
      (node (ref "J4") (pin "H9") (pinfunction "GND_H9") (pintype "passive"))
      (node (ref "J4") (pin "I1") (pinfunction "GND_I1") (pintype "passive"))
      (node (ref "J4") (pin "I11") (pinfunction "GND_I11") (pintype "passive"))
      (node (ref "J4") (pin "I14") (pinfunction "GND_I14") (pintype "passive"))
      (node (ref "J4") (pin "I17") (pinfunction "GND_I17") (pintype "passive"))
      (node (ref "J4") (pin "I20") (pinfunction "GND_I20") (pintype "passive"))
      (node (ref "J4") (pin "I23") (pinfunction "GND_I23") (pintype "passive"))
      (node (ref "J4") (pin "I26") (pinfunction "GND_I26") (pintype "passive"))
      (node (ref "J4") (pin "I29") (pinfunction "GND_I29") (pintype "passive"))
      (node (ref "J4") (pin "I32") (pinfunction "GND_I32") (pintype "passive"))
      (node (ref "J4") (pin "I35") (pinfunction "GND_I35") (pintype "passive"))
      (node (ref "J4") (pin "I38") (pinfunction "GND_I38") (pintype "passive"))
      (node (ref "J4") (pin "I4") (pinfunction "GND_I4") (pintype "passive"))
      (node (ref "J4") (pin "I40") (pinfunction "GND_I40") (pintype "passive"))
      (node (ref "J4") (pin "I5") (pinfunction "GND_I5") (pintype "passive"))
      (node (ref "J4") (pin "I8") (pinfunction "GND_I8") (pintype "passive"))
      (node (ref "J4") (pin "J12") (pinfunction "GND_J12") (pintype "passive"))
      (node (ref "J4") (pin "J15") (pinfunction "GND_J15") (pintype "passive"))
      (node (ref "J4") (pin "J18") (pinfunction "GND_J18") (pintype "passive"))
      (node (ref "J4") (pin "J2") (pinfunction "GND_J2") (pintype "passive"))
      (node (ref "J4") (pin "J21") (pinfunction "GND_J21") (pintype "passive"))
      (node (ref "J4") (pin "J24") (pinfunction "GND_J24") (pintype "passive"))
      (node (ref "J4") (pin "J27") (pinfunction "GND_J27") (pintype "passive"))
      (node (ref "J4") (pin "J3") (pinfunction "GND_J3") (pintype "passive"))
      (node (ref "J4") (pin "J30") (pinfunction "GND_J30") (pintype "passive"))
      (node (ref "J4") (pin "J33") (pinfunction "GND_J33") (pintype "passive"))
      (node (ref "J4") (pin "J36") (pinfunction "GND_J36") (pintype "passive"))
      (node (ref "J4") (pin "J39") (pinfunction "GND_J39") (pintype "passive"))
      (node (ref "J4") (pin "J6") (pinfunction "GND_J6") (pintype "passive"))
      (node (ref "J4") (pin "J9") (pinfunction "GND_J9") (pintype "passive"))
      (node (ref "J5") (pin "2") (pinfunction "2_2") (pintype "power_in"))
      (node (ref "J6") (pin "2") (pinfunction "2_2") (pintype "power_in"))
      (node (ref "R53") (pin "1") (pinfunction "1_1") (pintype "passive"))
      (node (ref "R54") (pin "1") (pinfunction "1_1") (pintype "passive"))
      (node (ref "U4") (pin "4") (pinfunction "GND_4") (pintype "power_in"))
      (node (ref "U5") (pin "1") (pinfunction "A0_1") (pintype "passive"))
      (node (ref "U5") (pin "12") (pinfunction "VSS_12") (pintype "passive"))
      (node (ref "U5") (pin "2") (pinfunction "A1_2") (pintype "passive"))
      (node (ref "U5") (pin "21") (pinfunction "A2_21") (pintype "passive"))
      (node (ref "U6") (pin "1") (pinfunction "1OEb_1") (pintype "input"))
      (node (ref "U6") (pin "10") (pinfunction "GND_10_10") (pintype "power_in"))
      (node (ref "U6") (pin "11") (pinfunction "GND_11_11") (pintype "power_in"))
      (node (ref "U6") (pin "16") (pinfunction "2OEb_16") (pintype "input"))
      (node (ref "U7") (pin "1") (pinfunction "1OEb_1") (pintype "input"))
      (node (ref "U7") (pin "10") (pinfunction "GND_10_10") (pintype "power_in"))
      (node (ref "U7") (pin "11") (pinfunction "GND_11_11") (pintype "power_in"))
      (node (ref "U7") (pin "16") (pinfunction "2OEb_16") (pintype "input"))
    )
    (net (code "71") (name "Net-(C83-Pad2)") (class "Default")
      (node (ref "C83") (pin "2") (pinfunction "2_2") (pintype "passive"))
      (node (ref "J5") (pin "1") (pinfunction "1_1") (pintype "output"))
    )
    (net (code "72") (name "Net-(C84-Pad2)") (class "Default")
      (node (ref "C84") (pin "2") (pinfunction "2_2") (pintype "passive"))
      (node (ref "J6") (pin "1") (pinfunction "1_1") (pintype "output"))
    )
    (net (code "73") (name "Net-(IC6-SDA)") (class "Default")
      (node (ref "IC6") (pin "5") (pinfunction "SDA_5") (pintype "bidirectional"))
      (node (ref "R53") (pin "2") (pinfunction "2_2") (pintype "passive"))
    )
    (net (code "74") (name "Net-(J4B-TDI)") (class "Default")
      (node (ref "J4") (pin "D30") (pinfunction "TDI_D30") (pintype "passive"))
      (node (ref "J4") (pin "D31") (pinfunction "TDO_D31") (pintype "passive"))
    )
    (net (code "75") (name "Net-(U4-OE)") (class "Default")
      (node (ref "R54") (pin "2") (pinfunction "2_2") (pintype "passive"))
      (node (ref "U4") (pin "5") (pinfunction "OE_5") (pintype "input"))
      (node (ref "W4") (pin "1") (pinfunction "1_1") (pintype "passive"))
    )
    (net (code "76") (name "Net-(U5-*RESET)") (class "Default")
      (node (ref "R56") (pin "1") (pinfunction "1_1") (pintype "passive"))
      (node (ref "U5") (pin "3") (pinfunction "*RESET_3") (pintype "passive"))
    )
    (net (code "77") (name "Net-(U6-1DIR)") (class "Default")
      (node (ref "R58") (pin "1") (pinfunction "1_1") (pintype "passive"))
      (node (ref "U6") (pin "4") (pinfunction "1DIR_4") (pintype "input"))
      (node (ref "U6") (pin "5") (pinfunction "2DIR_5") (pintype "input"))
    )
    (net (code "78") (name "Net-(U7-1DIR)") (class "Default")
      (node (ref "R59") (pin "1") (pinfunction "1_1") (pintype "passive"))
      (node (ref "U7") (pin "4") (pinfunction "1DIR_4") (pintype "input"))
      (node (ref "U7") (pin "5") (pinfunction "2DIR_5") (pintype "input"))
    )
    (net (code "79") (name "P3V3") (class "Default")
      (node (ref "C87") (pin "2") (pinfunction "2_2") (pintype "passive"))
      (node (ref "C88") (pin "2") (pinfunction "2_2") (pintype "passive"))
      (node (ref "C90") (pin "2") (pinfunction "2_2") (pintype "passive"))
      (node (ref "C92") (pin "2") (pinfunction "2_2") (pintype "passive"))
      (node (ref "J4") (pin "C39") (pinfunction "3P3V_C39") (pintype "passive"))
      (node (ref "J4") (pin "D36") (pinfunction "3P3V_D36") (pintype "passive"))
      (node (ref "J4") (pin "D38") (pinfunction "3P3V_D38") (pintype "passive"))
      (node (ref "J4") (pin "D40") (pinfunction "3P3V_D40") (pintype "passive"))
      (node (ref "R55") (pin "10") (pinfunction "10_10") (pintype "passive"))
      (node (ref "R55") (pin "11") (pinfunction "11_11") (pintype "passive"))
      (node (ref "R55") (pin "12") (pinfunction "12_12") (pintype "passive"))
      (node (ref "R55") (pin "13") (pinfunction "13_13") (pintype "passive"))
      (node (ref "R55") (pin "14") (pinfunction "14_14") (pintype "passive"))
      (node (ref "R55") (pin "15") (pinfunction "15_15") (pintype "passive"))
      (node (ref "R55") (pin "16") (pinfunction "16_16") (pintype "passive"))
      (node (ref "R55") (pin "9") (pinfunction "9_9") (pintype "passive"))
      (node (ref "R56") (pin "2") (pinfunction "2_2") (pintype "passive"))
      (node (ref "R57") (pin "1") (pinfunction "1_1") (pintype "passive"))
      (node (ref "R57") (pin "2") (pinfunction "2_2") (pintype "passive"))
      (node (ref "R57") (pin "3") (pinfunction "3_3") (pintype "passive"))
      (node (ref "R57") (pin "4") (pinfunction "4_4") (pintype "passive"))
      (node (ref "U4") (pin "8") (pinfunction "VCCB_8") (pintype "power_in"))
      (node (ref "U5") (pin "24") (pinfunction "VDD_24") (pintype "passive"))
      (node (ref "U6") (pin "2") (pinfunction "VCCB_2") (pintype "power_in"))
      (node (ref "U7") (pin "2") (pinfunction "VCCB_2") (pintype "power_in"))
    )
    (net (code "80") (name "P3V3A") (class "Default")
      (node (ref "C85") (pin "2") (pinfunction "2_2") (pintype "passive"))
      (node (ref "IC6") (pin "8") (pinfunction "VCC_8") (pintype "power_in"))
      (node (ref "J4") (pin "D32") (pinfunction "3P3VAUX_D32") (pintype "passive"))
      (node (ref "R51") (pin "2") (pinfunction "2_2") (pintype "passive"))
      (node (ref "R52") (pin "2") (pinfunction "2_2") (pintype "passive"))
    )
    (net (code "81") (name "P12V") (class "Default")
      (node (ref "J4") (pin "C35") (pinfunction "12P0V_C35") (pintype "passive"))
      (node (ref "J4") (pin "C37") (pinfunction "12P0V_C37") (pintype "passive"))
    )
    (net (code "82") (name "VADJ") (class "Default")
      (node (ref "C86") (pin "2") (pinfunction "2_2") (pintype "passive"))
      (node (ref "C89") (pin "2") (pinfunction "2_2") (pintype "passive"))
      (node (ref "C91") (pin "2") (pinfunction "2_2") (pintype "passive"))
      (node (ref "J4") (pin "E39") (pinfunction "VADJ_E39") (pintype "passive"))
      (node (ref "J4") (pin "F40") (pinfunction "VADJ_F40") (pintype "passive"))
      (node (ref "J4") (pin "G39") (pinfunction "VADJ_G39") (pintype "passive"))
      (node (ref "J4") (pin "H40") (pinfunction "VADJ_H40") (pintype "passive"))
      (node (ref "R58") (pin "2") (pinfunction "2_2") (pintype "passive"))
      (node (ref "R59") (pin "2") (pinfunction "2_2") (pintype "passive"))
      (node (ref "U4") (pin "1") (pinfunction "VCCA_1") (pintype "power_in"))
      (node (ref "U6") (pin "3") (pinfunction "VCCA_3") (pintype "power_in"))
      (node (ref "U7") (pin "3") (pinfunction "VCCA_3") (pintype "power_in"))
      (node (ref "W4") (pin "2") (pinfunction "2_2") (pintype "bidirectional"))
    )
    (net (code "83") (name "unconnected-(J4A-CLK_DIR-PadB1)") (class "Default")
      (node (ref "J4") (pin "B1") (pinfunction "CLK_DIR_B1") (pintype "passive"))
    )
    (net (code "84") (name "unconnected-(J4A-DP2_C2M_N-PadA27)") (class "Default")
      (node (ref "J4") (pin "A27") (pinfunction "DP2_C2M_N_A27") (pintype "passive"))
    )
    (net (code "85") (name "unconnected-(J4A-DP2_C2M_P-PadA26)") (class "Default")
      (node (ref "J4") (pin "A26") (pinfunction "DP2_C2M_P_A26") (pintype "passive"))
    )
    (net (code "86") (name "unconnected-(J4A-DP2_M2C_N-PadA7)") (class "Default")
      (node (ref "J4") (pin "A7") (pinfunction "DP2_M2C_N_A7") (pintype "passive"))
    )
    (net (code "87") (name "unconnected-(J4A-DP2_M2C_P-PadA6)") (class "Default")
      (node (ref "J4") (pin "A6") (pinfunction "DP2_M2C_P_A6") (pintype "passive"))
    )
    (net (code "88") (name "unconnected-(J4A-DP3_C2M_N-PadA31)") (class "Default")
      (node (ref "J4") (pin "A31") (pinfunction "DP3_C2M_N_A31") (pintype "passive"))
    )
    (net (code "89") (name "unconnected-(J4A-DP3_C2M_P-PadA30)") (class "Default")
      (node (ref "J4") (pin "A30") (pinfunction "DP3_C2M_P_A30") (pintype "passive"))
    )
    (net (code "90") (name "unconnected-(J4A-DP3_M2C_N-PadA11)") (class "Default")
      (node (ref "J4") (pin "A11") (pinfunction "DP3_M2C_N_A11") (pintype "passive"))
    )
    (net (code "91") (name "unconnected-(J4A-DP3_M2C_P-PadA10)") (class "Default")
      (node (ref "J4") (pin "A10") (pinfunction "DP3_M2C_P_A10") (pintype "passive"))
    )
    (net (code "92") (name "unconnected-(J4A-DP4_C2M_N-PadA35)") (class "Default")
      (node (ref "J4") (pin "A35") (pinfunction "DP4_C2M_N_A35") (pintype "passive"))
    )
    (net (code "93") (name "unconnected-(J4A-DP4_C2M_P-PadA34)") (class "Default")
      (node (ref "J4") (pin "A34") (pinfunction "DP4_C2M_P_A34") (pintype "passive"))
    )
    (net (code "94") (name "unconnected-(J4A-DP4_M2C_N-PadA15)") (class "Default")
      (node (ref "J4") (pin "A15") (pinfunction "DP4_M2C_N_A15") (pintype "passive"))
    )
    (net (code "95") (name "unconnected-(J4A-DP4_M2C_P-PadA14)") (class "Default")
      (node (ref "J4") (pin "A14") (pinfunction "DP4_M2C_P_A14") (pintype "passive"))
    )
    (net (code "96") (name "unconnected-(J4A-DP5_C2M_N-PadA39)") (class "Default")
      (node (ref "J4") (pin "A39") (pinfunction "DP5_C2M_N_A39") (pintype "passive"))
    )
    (net (code "97") (name "unconnected-(J4A-DP5_C2M_P-PadA38)") (class "Default")
      (node (ref "J4") (pin "A38") (pinfunction "DP5_C2M_P_A38") (pintype "passive"))
    )
    (net (code "98") (name "unconnected-(J4A-DP5_M2C_N-PadA19)") (class "Default")
      (node (ref "J4") (pin "A19") (pinfunction "DP5_M2C_N_A19") (pintype "passive"))
    )
    (net (code "99") (name "unconnected-(J4A-DP5_M2C_P-PadA18)") (class "Default")
      (node (ref "J4") (pin "A18") (pinfunction "DP5_M2C_P_A18") (pintype "passive"))
    )
    (net (code "100") (name "unconnected-(J4A-DP6_C2M_N-PadB37)") (class "Default")
      (node (ref "J4") (pin "B37") (pinfunction "DP6_C2M_N_B37") (pintype "passive"))
    )
    (net (code "101") (name "unconnected-(J4A-DP6_C2M_P-PadB36)") (class "Default")
      (node (ref "J4") (pin "B36") (pinfunction "DP6_C2M_P_B36") (pintype "passive"))
    )
    (net (code "102") (name "unconnected-(J4A-DP6_M2C_N-PadB17)") (class "Default")
      (node (ref "J4") (pin "B17") (pinfunction "DP6_M2C_N_B17") (pintype "passive"))
    )
    (net (code "103") (name "unconnected-(J4A-DP6_M2C_P-PadB16)") (class "Default")
      (node (ref "J4") (pin "B16") (pinfunction "DP6_M2C_P_B16") (pintype "passive"))
    )
    (net (code "104") (name "unconnected-(J4A-DP7_C2M_N-PadB33)") (class "Default")
      (node (ref "J4") (pin "B33") (pinfunction "DP7_C2M_N_B33") (pintype "passive"))
    )
    (net (code "105") (name "unconnected-(J4A-DP7_C2M_P-PadB32)") (class "Default")
      (node (ref "J4") (pin "B32") (pinfunction "DP7_C2M_P_B32") (pintype "passive"))
    )
    (net (code "106") (name "unconnected-(J4A-DP7_M2C_N-PadB13)") (class "Default")
      (node (ref "J4") (pin "B13") (pinfunction "DP7_M2C_N_B13") (pintype "passive"))
    )
    (net (code "107") (name "unconnected-(J4A-DP7_M2C_P-PadB12)") (class "Default")
      (node (ref "J4") (pin "B12") (pinfunction "DP7_M2C_P_B12") (pintype "passive"))
    )
    (net (code "108") (name "unconnected-(J4A-DP8_C2M_N-PadB29)") (class "Default")
      (node (ref "J4") (pin "B29") (pinfunction "DP8_C2M_N_B29") (pintype "passive"))
    )
    (net (code "109") (name "unconnected-(J4A-DP8_C2M_P-PadB28)") (class "Default")
      (node (ref "J4") (pin "B28") (pinfunction "DP8_C2M_P_B28") (pintype "passive"))
    )
    (net (code "110") (name "unconnected-(J4A-DP8_M2C_N-PadB9)") (class "Default")
      (node (ref "J4") (pin "B9") (pinfunction "DP8_M2C_N_B9") (pintype "passive"))
    )
    (net (code "111") (name "unconnected-(J4A-DP8_M2C_P-PadB8)") (class "Default")
      (node (ref "J4") (pin "B8") (pinfunction "DP8_M2C_P_B8") (pintype "passive"))
    )
    (net (code "112") (name "unconnected-(J4A-DP9_C2M_N-PadB25)") (class "Default")
      (node (ref "J4") (pin "B25") (pinfunction "DP9_C2M_N_B25") (pintype "passive"))
    )
    (net (code "113") (name "unconnected-(J4A-DP9_C2M_P-PadB24)") (class "Default")
      (node (ref "J4") (pin "B24") (pinfunction "DP9_C2M_P_B24") (pintype "passive"))
    )
    (net (code "114") (name "unconnected-(J4A-DP9_M2C_N-PadB5)") (class "Default")
      (node (ref "J4") (pin "B5") (pinfunction "DP9_M2C_N_B5") (pintype "passive"))
    )
    (net (code "115") (name "unconnected-(J4A-DP9_M2C_P-PadB4)") (class "Default")
      (node (ref "J4") (pin "B4") (pinfunction "DP9_M2C_P_B4") (pintype "passive"))
    )
    (net (code "116") (name "unconnected-(J4A-RES0-PadB40)") (class "Default")
      (node (ref "J4") (pin "B40") (pinfunction "RES0_B40") (pintype "passive"))
    )
    (net (code "117") (name "unconnected-(J4B-LA05_N-PadD12)") (class "Default")
      (node (ref "J4") (pin "D12") (pinfunction "LA05_N_D12") (pintype "passive"))
    )
    (net (code "118") (name "unconnected-(J4B-LA17_N_CC-PadD21)") (class "Default")
      (node (ref "J4") (pin "D21") (pinfunction "LA17_N_CC_D21") (pintype "passive"))
    )
    (net (code "119") (name "unconnected-(J4B-LA17_P_CC-PadD20)") (class "Default")
      (node (ref "J4") (pin "D20") (pinfunction "LA17_P_CC_D20") (pintype "passive"))
    )
    (net (code "120") (name "unconnected-(J4B-LA23_N-PadD24)") (class "Default")
      (node (ref "J4") (pin "D24") (pinfunction "LA23_N_D24") (pintype "passive"))
    )
    (net (code "121") (name "unconnected-(J4B-LA26_N-PadD27)") (class "Default")
      (node (ref "J4") (pin "D27") (pinfunction "LA26_N_D27") (pintype "passive"))
    )
    (net (code "122") (name "unconnected-(J4B-PG_C2M-PadD1)") (class "Default")
      (node (ref "J4") (pin "D1") (pinfunction "PG_C2M_D1") (pintype "passive"))
    )
    (net (code "123") (name "unconnected-(J4B-TCK-PadD29)") (class "Default")
      (node (ref "J4") (pin "D29") (pinfunction "TCK_D29") (pintype "passive"))
    )
    (net (code "124") (name "unconnected-(J4B-TMS-PadD33)") (class "Default")
      (node (ref "J4") (pin "D33") (pinfunction "TMS_D33") (pintype "passive"))
    )
    (net (code "125") (name "unconnected-(J4B-TRST_L-PadD34)") (class "Default")
      (node (ref "J4") (pin "D34") (pinfunction "TRST_L_D34") (pintype "passive"))
    )
    (net (code "126") (name "unconnected-(J4C-HA00_N_CC-PadF5)") (class "Default")
      (node (ref "J4") (pin "F5") (pinfunction "HA00_N_CC_F5") (pintype "passive"))
    )
    (net (code "127") (name "unconnected-(J4C-HA00_P_CC-PadF4)") (class "Default")
      (node (ref "J4") (pin "F4") (pinfunction "HA00_P_CC_F4") (pintype "passive"))
    )
    (net (code "128") (name "unconnected-(J4C-HA01_N_CC-PadE3)") (class "Default")
      (node (ref "J4") (pin "E3") (pinfunction "HA01_N_CC_E3") (pintype "passive"))
    )
    (net (code "129") (name "unconnected-(J4C-HA01_P_CC-PadE2)") (class "Default")
      (node (ref "J4") (pin "E2") (pinfunction "HA01_P_CC_E2") (pintype "passive"))
    )
    (net (code "130") (name "unconnected-(J4C-HA04_N-PadF8)") (class "Default")
      (node (ref "J4") (pin "F8") (pinfunction "HA04_N_F8") (pintype "passive"))
    )
    (net (code "131") (name "unconnected-(J4C-HA04_P-PadF7)") (class "Default")
      (node (ref "J4") (pin "F7") (pinfunction "HA04_P_F7") (pintype "passive"))
    )
    (net (code "132") (name "unconnected-(J4C-HA05_N-PadE7)") (class "Default")
      (node (ref "J4") (pin "E7") (pinfunction "HA05_N_E7") (pintype "passive"))
    )
    (net (code "133") (name "unconnected-(J4C-HA05_P-PadE6)") (class "Default")
      (node (ref "J4") (pin "E6") (pinfunction "HA05_P_E6") (pintype "passive"))
    )
    (net (code "134") (name "unconnected-(J4C-HA08_N-PadF11)") (class "Default")
      (node (ref "J4") (pin "F11") (pinfunction "HA08_N_F11") (pintype "passive"))
    )
    (net (code "135") (name "unconnected-(J4C-HA08_P-PadF10)") (class "Default")
      (node (ref "J4") (pin "F10") (pinfunction "HA08_P_F10") (pintype "passive"))
    )
    (net (code "136") (name "unconnected-(J4C-HA09_N-PadE10)") (class "Default")
      (node (ref "J4") (pin "E10") (pinfunction "HA09_N_E10") (pintype "passive"))
    )
    (net (code "137") (name "unconnected-(J4C-HA09_P-PadE9)") (class "Default")
      (node (ref "J4") (pin "E9") (pinfunction "HA09_P_E9") (pintype "passive"))
    )
    (net (code "138") (name "unconnected-(J4C-HA12_N-PadF14)") (class "Default")
      (node (ref "J4") (pin "F14") (pinfunction "HA12_N_F14") (pintype "passive"))
    )
    (net (code "139") (name "unconnected-(J4C-HA12_P-PadF13)") (class "Default")
      (node (ref "J4") (pin "F13") (pinfunction "HA12_P_F13") (pintype "passive"))
    )
    (net (code "140") (name "unconnected-(J4C-HA13_N-PadE13)") (class "Default")
      (node (ref "J4") (pin "E13") (pinfunction "HA13_N_E13") (pintype "passive"))
    )
    (net (code "141") (name "unconnected-(J4C-HA13_P-PadE12)") (class "Default")
      (node (ref "J4") (pin "E12") (pinfunction "HA13_P_E12") (pintype "passive"))
    )
    (net (code "142") (name "unconnected-(J4C-HA15_N-PadF17)") (class "Default")
      (node (ref "J4") (pin "F17") (pinfunction "HA15_N_F17") (pintype "passive"))
    )
    (net (code "143") (name "unconnected-(J4C-HA15_P-PadF16)") (class "Default")
      (node (ref "J4") (pin "F16") (pinfunction "HA15_P_F16") (pintype "passive"))
    )
    (net (code "144") (name "unconnected-(J4C-HA16_N-PadE16)") (class "Default")
      (node (ref "J4") (pin "E16") (pinfunction "HA16_N_E16") (pintype "passive"))
    )
    (net (code "145") (name "unconnected-(J4C-HA16_P-PadE15)") (class "Default")
      (node (ref "J4") (pin "E15") (pinfunction "HA16_P_E15") (pintype "passive"))
    )
    (net (code "146") (name "unconnected-(J4C-HA19_N-PadF20)") (class "Default")
      (node (ref "J4") (pin "F20") (pinfunction "HA19_N_F20") (pintype "passive"))
    )
    (net (code "147") (name "unconnected-(J4C-HA19_P-PadF19)") (class "Default")
      (node (ref "J4") (pin "F19") (pinfunction "HA19_P_F19") (pintype "passive"))
    )
    (net (code "148") (name "unconnected-(J4C-HA20_N-PadE19)") (class "Default")
      (node (ref "J4") (pin "E19") (pinfunction "HA20_N_E19") (pintype "passive"))
    )
    (net (code "149") (name "unconnected-(J4C-HA20_P-PadE18)") (class "Default")
      (node (ref "J4") (pin "E18") (pinfunction "HA20_P_E18") (pintype "passive"))
    )
    (net (code "150") (name "unconnected-(J4C-HB02_N-PadF23)") (class "Default")
      (node (ref "J4") (pin "F23") (pinfunction "HB02_N_F23") (pintype "passive"))
    )
    (net (code "151") (name "unconnected-(J4C-HB02_P-PadF22)") (class "Default")
      (node (ref "J4") (pin "F22") (pinfunction "HB02_P_F22") (pintype "passive"))
    )
    (net (code "152") (name "unconnected-(J4C-HB03_N-PadE22)") (class "Default")
      (node (ref "J4") (pin "E22") (pinfunction "HB03_N_E22") (pintype "passive"))
    )
    (net (code "153") (name "unconnected-(J4C-HB03_P-PadE21)") (class "Default")
      (node (ref "J4") (pin "E21") (pinfunction "HB03_P_E21") (pintype "passive"))
    )
    (net (code "154") (name "unconnected-(J4C-HB04_N-PadF26)") (class "Default")
      (node (ref "J4") (pin "F26") (pinfunction "HB04_N_F26") (pintype "passive"))
    )
    (net (code "155") (name "unconnected-(J4C-HB04_P-PadF25)") (class "Default")
      (node (ref "J4") (pin "F25") (pinfunction "HB04_P_F25") (pintype "passive"))
    )
    (net (code "156") (name "unconnected-(J4C-HB05_N-PadE25)") (class "Default")
      (node (ref "J4") (pin "E25") (pinfunction "HB05_N_E25") (pintype "passive"))
    )
    (net (code "157") (name "unconnected-(J4C-HB05_P-PadE24)") (class "Default")
      (node (ref "J4") (pin "E24") (pinfunction "HB05_P_E24") (pintype "passive"))
    )
    (net (code "158") (name "unconnected-(J4C-HB08_N-PadF29)") (class "Default")
      (node (ref "J4") (pin "F29") (pinfunction "HB08_N_F29") (pintype "passive"))
    )
    (net (code "159") (name "unconnected-(J4C-HB08_P-PadF28)") (class "Default")
      (node (ref "J4") (pin "F28") (pinfunction "HB08_P_F28") (pintype "passive"))
    )
    (net (code "160") (name "unconnected-(J4C-HB09_N-PadE28)") (class "Default")
      (node (ref "J4") (pin "E28") (pinfunction "HB09_N_E28") (pintype "passive"))
    )
    (net (code "161") (name "unconnected-(J4C-HB09_P-PadE27)") (class "Default")
      (node (ref "J4") (pin "E27") (pinfunction "HB09_P_E27") (pintype "passive"))
    )
    (net (code "162") (name "unconnected-(J4C-HB12_N-PadF32)") (class "Default")
      (node (ref "J4") (pin "F32") (pinfunction "HB12_N_F32") (pintype "passive"))
    )
    (net (code "163") (name "unconnected-(J4C-HB12_P-PadF31)") (class "Default")
      (node (ref "J4") (pin "F31") (pinfunction "HB12_P_F31") (pintype "passive"))
    )
    (net (code "164") (name "unconnected-(J4C-HB13_N-PadE31)") (class "Default")
      (node (ref "J4") (pin "E31") (pinfunction "HB13_N_E31") (pintype "passive"))
    )
    (net (code "165") (name "unconnected-(J4C-HB13_P-PadE30)") (class "Default")
      (node (ref "J4") (pin "E30") (pinfunction "HB13_P_E30") (pintype "passive"))
    )
    (net (code "166") (name "unconnected-(J4C-HB16_N-PadF35)") (class "Default")
      (node (ref "J4") (pin "F35") (pinfunction "HB16_N_F35") (pintype "passive"))
    )
    (net (code "167") (name "unconnected-(J4C-HB16_P-PadF34)") (class "Default")
      (node (ref "J4") (pin "F34") (pinfunction "HB16_P_F34") (pintype "passive"))
    )
    (net (code "168") (name "unconnected-(J4C-HB19_N-PadE34)") (class "Default")
      (node (ref "J4") (pin "E34") (pinfunction "HB19_N_E34") (pintype "passive"))
    )
    (net (code "169") (name "unconnected-(J4C-HB19_P-PadE33)") (class "Default")
      (node (ref "J4") (pin "E33") (pinfunction "HB19_P_E33") (pintype "passive"))
    )
    (net (code "170") (name "unconnected-(J4C-HB20_N-PadF38)") (class "Default")
      (node (ref "J4") (pin "F38") (pinfunction "HB20_N_F38") (pintype "passive"))
    )
    (net (code "171") (name "unconnected-(J4C-HB20_P-PadF37)") (class "Default")
      (node (ref "J4") (pin "F37") (pinfunction "HB20_P_F37") (pintype "passive"))
    )
    (net (code "172") (name "unconnected-(J4C-HB21_N-PadE37)") (class "Default")
      (node (ref "J4") (pin "E37") (pinfunction "HB21_N_E37") (pintype "passive"))
    )
    (net (code "173") (name "unconnected-(J4C-HB21_P-PadE36)") (class "Default")
      (node (ref "J4") (pin "E36") (pinfunction "HB21_P_E36") (pintype "passive"))
    )
    (net (code "174") (name "unconnected-(J4C-PG_M2C-PadF1)") (class "Default")
      (node (ref "J4") (pin "F1") (pinfunction "PG_M2C_F1") (pintype "passive"))
    )
    (net (code "175") (name "unconnected-(J4D-CLK1_M2C_N-PadG3)") (class "Default")
      (node (ref "J4") (pin "G3") (pinfunction "CLK1_M2C_N_G3") (pintype "passive"))
    )
    (net (code "176") (name "unconnected-(J4D-CLK1_M2C_P-PadG2)") (class "Default")
      (node (ref "J4") (pin "G2") (pinfunction "CLK1_M2C_P_G2") (pintype "passive"))
    )
    (net (code "177") (name "unconnected-(J4D-LA02_N-PadH8)") (class "Default")
      (node (ref "J4") (pin "H8") (pinfunction "LA02_N_H8") (pintype "passive"))
    )
    (net (code "178") (name "unconnected-(J4D-LA02_P-PadH7)") (class "Default")
      (node (ref "J4") (pin "H7") (pinfunction "LA02_P_H7") (pintype "passive"))
    )
    (net (code "179") (name "unconnected-(J4D-LA11_N-PadH17)") (class "Default")
      (node (ref "J4") (pin "H17") (pinfunction "LA11_N_H17") (pintype "passive"))
    )
    (net (code "180") (name "unconnected-(J4D-LA11_P-PadH16)") (class "Default")
      (node (ref "J4") (pin "H16") (pinfunction "LA11_P_H16") (pintype "passive"))
    )
    (net (code "181") (name "unconnected-(J4D-LA12_N-PadG16)") (class "Default")
      (node (ref "J4") (pin "G16") (pinfunction "LA12_N_G16") (pintype "passive"))
    )
    (net (code "182") (name "unconnected-(J4D-LA12_P-PadG15)") (class "Default")
      (node (ref "J4") (pin "G15") (pinfunction "LA12_P_G15") (pintype "passive"))
    )
    (net (code "183") (name "unconnected-(J4D-LA15_N-PadH20)") (class "Default")
      (node (ref "J4") (pin "H20") (pinfunction "LA15_N_H20") (pintype "passive"))
    )
    (net (code "184") (name "unconnected-(J4D-LA15_P-PadH19)") (class "Default")
      (node (ref "J4") (pin "H19") (pinfunction "LA15_P_H19") (pintype "passive"))
    )
    (net (code "185") (name "unconnected-(J4D-LA16_N-PadG19)") (class "Default")
      (node (ref "J4") (pin "G19") (pinfunction "LA16_N_G19") (pintype "passive"))
    )
    (net (code "186") (name "unconnected-(J4D-LA16_P-PadG18)") (class "Default")
      (node (ref "J4") (pin "G18") (pinfunction "LA16_P_G18") (pintype "passive"))
    )
    (net (code "187") (name "unconnected-(J4D-LA19_N-PadH23)") (class "Default")
      (node (ref "J4") (pin "H23") (pinfunction "LA19_N_H23") (pintype "passive"))
    )
    (net (code "188") (name "unconnected-(J4D-LA19_P-PadH22)") (class "Default")
      (node (ref "J4") (pin "H22") (pinfunction "LA19_P_H22") (pintype "passive"))
    )
    (net (code "189") (name "unconnected-(J4D-LA20_N-PadG22)") (class "Default")
      (node (ref "J4") (pin "G22") (pinfunction "LA20_N_G22") (pintype "passive"))
    )
    (net (code "190") (name "unconnected-(J4D-LA20_P-PadG21)") (class "Default")
      (node (ref "J4") (pin "G21") (pinfunction "LA20_P_G21") (pintype "passive"))
    )
    (net (code "191") (name "unconnected-(J4D-LA21_N-PadH26)") (class "Default")
      (node (ref "J4") (pin "H26") (pinfunction "LA21_N_H26") (pintype "passive"))
    )
    (net (code "192") (name "unconnected-(J4D-LA21_P-PadH25)") (class "Default")
      (node (ref "J4") (pin "H25") (pinfunction "LA21_P_H25") (pintype "passive"))
    )
    (net (code "193") (name "unconnected-(J4D-LA22_N-PadG25)") (class "Default")
      (node (ref "J4") (pin "G25") (pinfunction "LA22_N_G25") (pintype "passive"))
    )
    (net (code "194") (name "unconnected-(J4D-LA22_P-PadG24)") (class "Default")
      (node (ref "J4") (pin "G24") (pinfunction "LA22_P_G24") (pintype "passive"))
    )
    (net (code "195") (name "unconnected-(J4D-LA24_N-PadH29)") (class "Default")
      (node (ref "J4") (pin "H29") (pinfunction "LA24_N_H29") (pintype "passive"))
    )
    (net (code "196") (name "unconnected-(J4D-LA24_P-PadH28)") (class "Default")
      (node (ref "J4") (pin "H28") (pinfunction "LA24_P_H28") (pintype "passive"))
    )
    (net (code "197") (name "unconnected-(J4D-LA25_N-PadG28)") (class "Default")
      (node (ref "J4") (pin "G28") (pinfunction "LA25_N_G28") (pintype "passive"))
    )
    (net (code "198") (name "unconnected-(J4D-LA25_P-PadG27)") (class "Default")
      (node (ref "J4") (pin "G27") (pinfunction "LA25_P_G27") (pintype "passive"))
    )
    (net (code "199") (name "unconnected-(J4D-LA28_N-PadH32)") (class "Default")
      (node (ref "J4") (pin "H32") (pinfunction "LA28_N_H32") (pintype "passive"))
    )
    (net (code "200") (name "unconnected-(J4D-LA28_P-PadH31)") (class "Default")
      (node (ref "J4") (pin "H31") (pinfunction "LA28_P_H31") (pintype "passive"))
    )
    (net (code "201") (name "unconnected-(J4D-LA29_N-PadG31)") (class "Default")
      (node (ref "J4") (pin "G31") (pinfunction "LA29_N_G31") (pintype "passive"))
    )
    (net (code "202") (name "unconnected-(J4D-LA29_P-PadG30)") (class "Default")
      (node (ref "J4") (pin "G30") (pinfunction "LA29_P_G30") (pintype "passive"))
    )
    (net (code "203") (name "unconnected-(J4D-LA30_N-PadH35)") (class "Default")
      (node (ref "J4") (pin "H35") (pinfunction "LA30_N_H35") (pintype "passive"))
    )
    (net (code "204") (name "unconnected-(J4D-LA30_P-PadH34)") (class "Default")
      (node (ref "J4") (pin "H34") (pinfunction "LA30_P_H34") (pintype "passive"))
    )
    (net (code "205") (name "unconnected-(J4D-LA31_N-PadG34)") (class "Default")
      (node (ref "J4") (pin "G34") (pinfunction "LA31_N_G34") (pintype "passive"))
    )
    (net (code "206") (name "unconnected-(J4D-LA31_P-PadG33)") (class "Default")
      (node (ref "J4") (pin "G33") (pinfunction "LA31_P_G33") (pintype "passive"))
    )
    (net (code "207") (name "unconnected-(J4D-LA32_N-PadH38)") (class "Default")
      (node (ref "J4") (pin "H38") (pinfunction "LA32_N_H38") (pintype "passive"))
    )
    (net (code "208") (name "unconnected-(J4D-LA32_P-PadH37)") (class "Default")
      (node (ref "J4") (pin "H37") (pinfunction "LA32_P_H37") (pintype "passive"))
    )
    (net (code "209") (name "unconnected-(J4D-LA33_N-PadG37)") (class "Default")
      (node (ref "J4") (pin "G37") (pinfunction "LA33_N_G37") (pintype "passive"))
    )
    (net (code "210") (name "unconnected-(J4D-LA33_P-PadG36)") (class "Default")
      (node (ref "J4") (pin "G36") (pinfunction "LA33_P_G36") (pintype "passive"))
    )
    (net (code "211") (name "unconnected-(J4D-PRSNT_M2C_L-PadH2)") (class "Default")
      (node (ref "J4") (pin "H2") (pinfunction "PRSNT_M2C_L_H2") (pintype "passive"))
    )
    (net (code "212") (name "unconnected-(J4D-VREF_A_M2C-PadH1)") (class "Default")
      (node (ref "J4") (pin "H1") (pinfunction "VREF_A_M2C_H1") (pintype "passive"))
    )
    (net (code "213") (name "unconnected-(J4E-CLK2_BIDIR_N-PadJ5)") (class "Default")
      (node (ref "J4") (pin "J5") (pinfunction "CLK2_BIDIR_N_J5") (pintype "passive"))
    )
    (net (code "214") (name "unconnected-(J4E-CLK2_BIDIR_P-PadJ4)") (class "Default")
      (node (ref "J4") (pin "J4") (pinfunction "CLK2_BIDIR_P_J4") (pintype "passive"))
    )
    (net (code "215") (name "unconnected-(J4E-CLK3_BIDIR_N-PadI3)") (class "Default")
      (node (ref "J4") (pin "I3") (pinfunction "CLK3_BIDIR_N_I3") (pintype "passive"))
    )
    (net (code "216") (name "unconnected-(J4E-CLK3_BIDIR_P-PadI2)") (class "Default")
      (node (ref "J4") (pin "I2") (pinfunction "CLK3_BIDIR_P_I2") (pintype "passive"))
    )
    (net (code "217") (name "unconnected-(J4E-HA02_N-PadJ8)") (class "Default")
      (node (ref "J4") (pin "J8") (pinfunction "HA02_N_J8") (pintype "passive"))
    )
    (net (code "218") (name "unconnected-(J4E-HA02_P-PadJ7)") (class "Default")
      (node (ref "J4") (pin "J7") (pinfunction "HA02_P_J7") (pintype "passive"))
    )
    (net (code "219") (name "unconnected-(J4E-HA03_N-PadI7)") (class "Default")
      (node (ref "J4") (pin "I7") (pinfunction "HA03_N_I7") (pintype "passive"))
    )
    (net (code "220") (name "unconnected-(J4E-HA03_P-PadI6)") (class "Default")
      (node (ref "J4") (pin "I6") (pinfunction "HA03_P_I6") (pintype "passive"))
    )
    (net (code "221") (name "unconnected-(J4E-HA06_N-PadJ11)") (class "Default")
      (node (ref "J4") (pin "J11") (pinfunction "HA06_N_J11") (pintype "passive"))
    )
    (net (code "222") (name "unconnected-(J4E-HA06_P-PadJ10)") (class "Default")
      (node (ref "J4") (pin "J10") (pinfunction "HA06_P_J10") (pintype "passive"))
    )
    (net (code "223") (name "unconnected-(J4E-HA07_N-PadI10)") (class "Default")
      (node (ref "J4") (pin "I10") (pinfunction "HA07_N_I10") (pintype "passive"))
    )
    (net (code "224") (name "unconnected-(J4E-HA07_P-PadI9)") (class "Default")
      (node (ref "J4") (pin "I9") (pinfunction "HA07_P_I9") (pintype "passive"))
    )
    (net (code "225") (name "unconnected-(J4E-HA10_N-PadJ14)") (class "Default")
      (node (ref "J4") (pin "J14") (pinfunction "HA10_N_J14") (pintype "passive"))
    )
    (net (code "226") (name "unconnected-(J4E-HA10_P-PadJ13)") (class "Default")
      (node (ref "J4") (pin "J13") (pinfunction "HA10_P_J13") (pintype "passive"))
    )
    (net (code "227") (name "unconnected-(J4E-HA11_N-PadI13)") (class "Default")
      (node (ref "J4") (pin "I13") (pinfunction "HA11_N_I13") (pintype "passive"))
    )
    (net (code "228") (name "unconnected-(J4E-HA11_P-PadI12)") (class "Default")
      (node (ref "J4") (pin "I12") (pinfunction "HA11_P_I12") (pintype "passive"))
    )
    (net (code "229") (name "unconnected-(J4E-HA14_N-PadI16)") (class "Default")
      (node (ref "J4") (pin "I16") (pinfunction "HA14_N_I16") (pintype "passive"))
    )
    (net (code "230") (name "unconnected-(J4E-HA14_P-PadI15)") (class "Default")
      (node (ref "J4") (pin "I15") (pinfunction "HA14_P_I15") (pintype "passive"))
    )
    (net (code "231") (name "unconnected-(J4E-HA17_N_CC-PadJ17)") (class "Default")
      (node (ref "J4") (pin "J17") (pinfunction "HA17_N_CC_J17") (pintype "passive"))
    )
    (net (code "232") (name "unconnected-(J4E-HA17_P_CC-PadJ16)") (class "Default")
      (node (ref "J4") (pin "J16") (pinfunction "HA17_P_CC_J16") (pintype "passive"))
    )
    (net (code "233") (name "unconnected-(J4E-HA18_N-PadI19)") (class "Default")
      (node (ref "J4") (pin "I19") (pinfunction "HA18_N_I19") (pintype "passive"))
    )
    (net (code "234") (name "unconnected-(J4E-HA18_P-PadI18)") (class "Default")
      (node (ref "J4") (pin "I18") (pinfunction "HA18_P_I18") (pintype "passive"))
    )
    (net (code "235") (name "unconnected-(J4E-HA21_N-PadJ20)") (class "Default")
      (node (ref "J4") (pin "J20") (pinfunction "HA21_N_J20") (pintype "passive"))
    )
    (net (code "236") (name "unconnected-(J4E-HA21_P-PadJ19)") (class "Default")
      (node (ref "J4") (pin "J19") (pinfunction "HA21_P_J19") (pintype "passive"))
    )
    (net (code "237") (name "unconnected-(J4E-HA22_N-PadI22)") (class "Default")
      (node (ref "J4") (pin "I22") (pinfunction "HA22_N_I22") (pintype "passive"))
    )
    (net (code "238") (name "unconnected-(J4E-HA22_P-PadI21)") (class "Default")
      (node (ref "J4") (pin "I21") (pinfunction "HA22_P_I21") (pintype "passive"))
    )
    (net (code "239") (name "unconnected-(J4E-HA23_N-PadJ23)") (class "Default")
      (node (ref "J4") (pin "J23") (pinfunction "HA23_N_J23") (pintype "passive"))
    )
    (net (code "240") (name "unconnected-(J4E-HA23_P-PadJ22)") (class "Default")
      (node (ref "J4") (pin "J22") (pinfunction "HA23_P_J22") (pintype "passive"))
    )
    (net (code "241") (name "unconnected-(J4E-HB00_N_CC-PadJ26)") (class "Default")
      (node (ref "J4") (pin "J26") (pinfunction "HB00_N_CC_J26") (pintype "passive"))
    )
    (net (code "242") (name "unconnected-(J4E-HB00_P_CC-PadJ25)") (class "Default")
      (node (ref "J4") (pin "J25") (pinfunction "HB00_P_CC_J25") (pintype "passive"))
    )
    (net (code "243") (name "unconnected-(J4E-HB01_N-PadI25)") (class "Default")
      (node (ref "J4") (pin "I25") (pinfunction "HB01_N_I25") (pintype "passive"))
    )
    (net (code "244") (name "unconnected-(J4E-HB01_P-PadI24)") (class "Default")
      (node (ref "J4") (pin "I24") (pinfunction "HB01_P_I24") (pintype "passive"))
    )
    (net (code "245") (name "unconnected-(J4E-HB06_N_CC-PadJ29)") (class "Default")
      (node (ref "J4") (pin "J29") (pinfunction "HB06_N_CC_J29") (pintype "passive"))
    )
    (net (code "246") (name "unconnected-(J4E-HB06_P_CC-PadJ28)") (class "Default")
      (node (ref "J4") (pin "J28") (pinfunction "HB06_P_CC_J28") (pintype "passive"))
    )
    (net (code "247") (name "unconnected-(J4E-HB07_N-PadI28)") (class "Default")
      (node (ref "J4") (pin "I28") (pinfunction "HB07_N_I28") (pintype "passive"))
    )
    (net (code "248") (name "unconnected-(J4E-HB07_P-PadI27)") (class "Default")
      (node (ref "J4") (pin "I27") (pinfunction "HB07_P_I27") (pintype "passive"))
    )
    (net (code "249") (name "unconnected-(J4E-HB10_N-PadJ32)") (class "Default")
      (node (ref "J4") (pin "J32") (pinfunction "HB10_N_J32") (pintype "passive"))
    )
    (net (code "250") (name "unconnected-(J4E-HB10_P-PadJ31)") (class "Default")
      (node (ref "J4") (pin "J31") (pinfunction "HB10_P_J31") (pintype "passive"))
    )
    (net (code "251") (name "unconnected-(J4E-HB11_N-PadI31)") (class "Default")
      (node (ref "J4") (pin "I31") (pinfunction "HB11_N_I31") (pintype "passive"))
    )
    (net (code "252") (name "unconnected-(J4E-HB11_P-PadI30)") (class "Default")
      (node (ref "J4") (pin "I30") (pinfunction "HB11_P_I30") (pintype "passive"))
    )
    (net (code "253") (name "unconnected-(J4E-HB14_N-PadJ35)") (class "Default")
      (node (ref "J4") (pin "J35") (pinfunction "HB14_N_J35") (pintype "passive"))
    )
    (net (code "254") (name "unconnected-(J4E-HB14_P-PadJ34)") (class "Default")
      (node (ref "J4") (pin "J34") (pinfunction "HB14_P_J34") (pintype "passive"))
    )
    (net (code "255") (name "unconnected-(J4E-HB15_N-PadI34)") (class "Default")
      (node (ref "J4") (pin "I34") (pinfunction "HB15_N_I34") (pintype "passive"))
    )
    (net (code "256") (name "unconnected-(J4E-HB15_P-PadI33)") (class "Default")
      (node (ref "J4") (pin "I33") (pinfunction "HB15_P_I33") (pintype "passive"))
    )
    (net (code "257") (name "unconnected-(J4E-HB17_N_CC-PadJ38)") (class "Default")
      (node (ref "J4") (pin "J38") (pinfunction "HB17_N_CC_J38") (pintype "passive"))
    )
    (net (code "258") (name "unconnected-(J4E-HB17_P_CC-PadJ37)") (class "Default")
      (node (ref "J4") (pin "J37") (pinfunction "HB17_P_CC_J37") (pintype "passive"))
    )
    (net (code "259") (name "unconnected-(J4E-HB18_N-PadI37)") (class "Default")
      (node (ref "J4") (pin "I37") (pinfunction "HB18_N_I37") (pintype "passive"))
    )
    (net (code "260") (name "unconnected-(J4E-HB18_P-PadI36)") (class "Default")
      (node (ref "J4") (pin "I36") (pinfunction "HB18_P_I36") (pintype "passive"))
    )
    (net (code "261") (name "unconnected-(J4E-VIO_B_M2C-PadI39)") (class "Default")
      (node (ref "J4") (pin "I39") (pinfunction "VIO_B_M2C_I39") (pintype "passive"))
    )
    (net (code "262") (name "unconnected-(J4E-VIO_B_M2C-PadJ40)") (class "Default")
      (node (ref "J4") (pin "J40") (pinfunction "VIO_B_M2C_J40") (pintype "passive"))
    )
    (net (code "263") (name "unconnected-(J4E-VREF_B_M2C-PadJ1)") (class "Default")
      (node (ref "J4") (pin "J1") (pinfunction "VREF_B_M2C_J1") (pintype "passive"))
    )
    (net (code "264") (name "unconnected-(U5-SC6-Pad18)") (class "Default")
      (node (ref "U5") (pin "18") (pinfunction "SC6_18") (pintype "passive+no_connect"))
    )
    (net (code "265") (name "unconnected-(U5-SC7-Pad20)") (class "Default")
      (node (ref "U5") (pin "20") (pinfunction "SC7_20") (pintype "passive+no_connect"))
    )
    (net (code "266") (name "unconnected-(U5-SD6-Pad17)") (class "Default")
      (node (ref "U5") (pin "17") (pinfunction "SD6_17") (pintype "passive+no_connect"))
    )
    (net (code "267") (name "unconnected-(U5-SD7-Pad19)") (class "Default")
      (node (ref "U5") (pin "19") (pinfunction "SD7_19") (pintype "passive+no_connect"))
    )
  )
)
